# Power_Supplies.net
KiCad netlist of a schematic drawn in Altium Designer
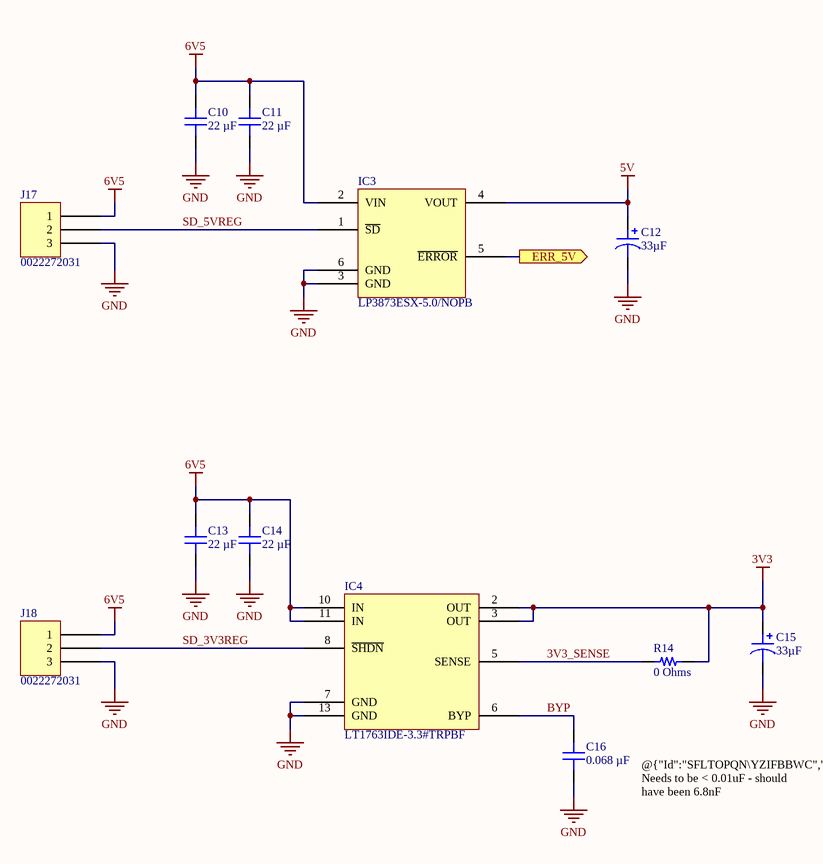
[diagram p0: Power Supplies.SchDoc]

(export (version "E")
  (design (tool "Eeschema 10.0.6"))
  (components
    (comp (ref "C10")
      (value "22 µF")
      (footprint "CAP 1210_3225 - 1MM")
      (description "CAP CER 22UF 25V X7R 1210")
      (fields
        (field (name "PART NUMBER") "CL32B226KAJNNNE")
        (field (name "MANUFACTURER") "Samsung Electro-Mechanics")
      )
      (libsource (lib "altiumlibrary.com") (part "Capacitor"))
    )
    (comp (ref "C11")
      (value "22 µF")
      (footprint "CAP 1210_3225 - 1MM")
      (description "CAP CER 22UF 25V X7R 1210")
      (fields
        (field (name "PART NUMBER") "CL32B226KAJNNNE")
        (field (name "MANUFACTURER") "Samsung Electro-Mechanics")
      )
      (libsource (lib "altiumlibrary.com") (part "Capacitor"))
    )
    (comp (ref "C12")
      (value "33µF")
      (footprint "CAP POL 1411_3528")
      (description "CAP TANT 33UF 10% 16V 1411")
      (fields (field (name "PART NUMBER") "TAJB336K016RNJ") (field (name "MANUFACTURER") "AVX Corporation"))
      (libsource (lib "altiumlibrary.com") (part "Polarised Capacitor"))
    )
    (comp (ref "C13")
      (value "22 µF")
      (footprint "CAP 1210_3225 - 1MM")
      (description "CAP CER 22UF 25V X7R 1210")
      (fields
        (field (name "PART NUMBER") "CL32B226KAJNNNE")
        (field (name "MANUFACTURER") "Samsung Electro-Mechanics")
      )
      (libsource (lib "altiumlibrary.com") (part "Capacitor"))
    )
    (comp (ref "C14")
      (value "22 µF")
      (footprint "CAP 1210_3225 - 1MM")
      (description "CAP CER 22UF 25V X7R 1210")
      (fields
        (field (name "PART NUMBER") "CL32B226KAJNNNE")
        (field (name "MANUFACTURER") "Samsung Electro-Mechanics")
      )
      (libsource (lib "altiumlibrary.com") (part "Capacitor"))
    )
    (comp (ref "C15")
      (value "33µF")
      (footprint "CAP POL 1411_3528")
      (description "CAP TANT 33UF 10% 16V 1411")
      (fields (field (name "PART NUMBER") "TAJB336K016RNJ") (field (name "MANUFACTURER") "AVX Corporation"))
      (libsource (lib "altiumlibrary.com") (part "Polarised Capacitor"))
    )
    (comp (ref "C16")
      (value "0.068 µF")
      (footprint "CAP 0402_1005")
      (description "CAP CER 0.068UF 50V X7R 0402")
      (fields
        (field (name "PART NUMBER") "GCM155R71H683KE02D")
        (field (name "MANUFACTURER") "Murata Electronics")
      )
      (libsource (lib "altiumlibrary.com") (part "Capacitor"))
    )
    (comp (ref "IC3")
      (value "LP3873ESX-5.0/NOPB")
      (footprint "TI DDPAK-5 KTT R-PSFM-G5")
      (description "IC REG LIN 5V 3A DDPAK/TO263-5")
      (fields (field (name "MANUFACTURER") "Texas Instruments"))
      (libsource (lib "altiumlibrary.com") (part "TI LP3873ESX KTT0005B"))
    )
    (comp (ref "IC4")
      (value "LT1763IDE-3.3#TRPBF")
      (footprint "ANALOG DFN-12 DE UE 05-08-1695 Rev D")
      (description "IC REG LINEAR 3.3V 500MA 12DFN")
      (fields (field (name "MANUFACTURER") "Analog Devices Inc."))
      (libsource (lib "altiumlibrary.com") (part "ANALOG LT1763 DE FIXED"))
    )
    (comp (ref "J17")
      (value "0022272031")
      (footprint "MOLEX KK 0022272031")
      (description "CONN HEADER VERT 3POS 2.54MM")
      (fields (field (name "MANUFACTURER") "Molex"))
      (libsource (lib "altiumlibrary.com") (part "3 Pin"))
    )
    (comp (ref "J18")
      (value "0022272031")
      (footprint "MOLEX KK 0022272031")
      (description "CONN HEADER VERT 3POS 2.54MM")
      (fields (field (name "MANUFACTURER") "Molex"))
      (libsource (lib "altiumlibrary.com") (part "3 Pin"))
    )
    (comp (ref "R14")
      (value "0 Ohms")
      (footprint "RES 0603_1608")
      (description "RES SMD 0 OHM JUMPER 1/10W 0603")
      (fields
        (field (name "PART NUMBER") "ERJ-3GEY0R00V")
        (field (name "MANUFACTURER") "Panasonic Electronic Components")
      )
      (libsource (lib "altiumlibrary.com") (part "Resistor"))
    )
  )
  (nets
    (net (code "1") (name "/3V3_SENSE") (class "Default")
      (node (ref "IC4") (pin "5") (pinfunction "SENSE_5") (pintype "passive"))
      (node (ref "R14") (pin "2") (pinfunction "2_2") (pintype "passive"))
    )
    (net (code "2") (name "/BYP") (class "Default")
      (node (ref "C16") (pin "2") (pinfunction "2_2") (pintype "passive"))
      (node (ref "IC4") (pin "6") (pinfunction "BYP_6") (pintype "passive"))
    )
    (net (code "3") (name "/ERR_5V") (class "Default")
      (node (ref "IC3") (pin "5") (pinfunction "~{ERROR}_5") (pintype "passive"))
    )
    (net (code "4") (name "/SD_3V3REG") (class "Default")
      (node (ref "IC4") (pin "8") (pinfunction "~{SHDN}_8") (pintype "passive"))
      (node (ref "J18") (pin "2") (pinfunction "2_2") (pintype "passive"))
    )
    (net (code "5") (name "/SD_5VREG") (class "Default")
      (node (ref "IC3") (pin "1") (pinfunction "~{SD}_1") (pintype "passive"))
      (node (ref "J17") (pin "2") (pinfunction "2_2") (pintype "passive"))
    )
    (net (code "6") (name "3V3") (class "Default")
      (node (ref "C15") (pin "1") (pinfunction "1_1") (pintype "passive"))
      (node (ref "IC4") (pin "2") (pinfunction "OUT_2") (pintype "passive"))
      (node (ref "IC4") (pin "3") (pinfunction "OUT_3") (pintype "passive"))
      (node (ref "R14") (pin "1") (pinfunction "1_1") (pintype "passive"))
    )
    (net (code "7") (name "5V") (class "Default")
      (node (ref "C12") (pin "1") (pinfunction "1_1") (pintype "passive"))
      (node (ref "IC3") (pin "4") (pinfunction "VOUT_4") (pintype "passive"))
    )
    (net (code "8") (name "6V5") (class "Default")
      (node (ref "C10") (pin "2") (pinfunction "2_2") (pintype "passive"))
      (node (ref "C11") (pin "2") (pinfunction "2_2") (pintype "passive"))
      (node (ref "C13") (pin "2") (pinfunction "2_2") (pintype "passive"))
      (node (ref "C14") (pin "2") (pinfunction "2_2") (pintype "passive"))
      (node (ref "IC3") (pin "2") (pinfunction "VIN_2") (pintype "passive"))
      (node (ref "IC4") (pin "10") (pinfunction "IN_10") (pintype "passive"))
      (node (ref "IC4") (pin "11") (pinfunction "IN_11") (pintype "passive"))
      (node (ref "J17") (pin "1") (pinfunction "1_1") (pintype "passive"))
      (node (ref "J18") (pin "1") (pinfunction "1_1") (pintype "passive"))
    )
    (net (code "9") (name "GND") (class "Default")
      (node (ref "C10") (pin "1") (pinfunction "1_1") (pintype "passive"))
      (node (ref "C11") (pin "1") (pinfunction "1_1") (pintype "passive"))
      (node (ref "C12") (pin "2") (pinfunction "2_2") (pintype "passive"))
      (node (ref "C13") (pin "1") (pinfunction "1_1") (pintype "passive"))
      (node (ref "C14") (pin "1") (pinfunction "1_1") (pintype "passive"))
      (node (ref "C15") (pin "2") (pinfunction "2_2") (pintype "passive"))
      (node (ref "C16") (pin "1") (pinfunction "1_1") (pintype "passive"))
      (node (ref "IC3") (pin "3") (pinfunction "GND_3") (pintype "passive"))
      (node (ref "IC3") (pin "6") (pinfunction "GND_6") (pintype "passive"))
      (node (ref "IC4") (pin "13") (pinfunction "GND_13") (pintype "passive"))
      (node (ref "IC4") (pin "7") (pinfunction "GND_7") (pintype "passive"))
      (node (ref "J17") (pin "3") (pinfunction "3_3") (pintype "passive"))
      (node (ref "J18") (pin "3") (pinfunction "3_3") (pintype "passive"))
    )
  )
)
